# single100.net
KiCad netlist of a schematic drawn in EAGLE
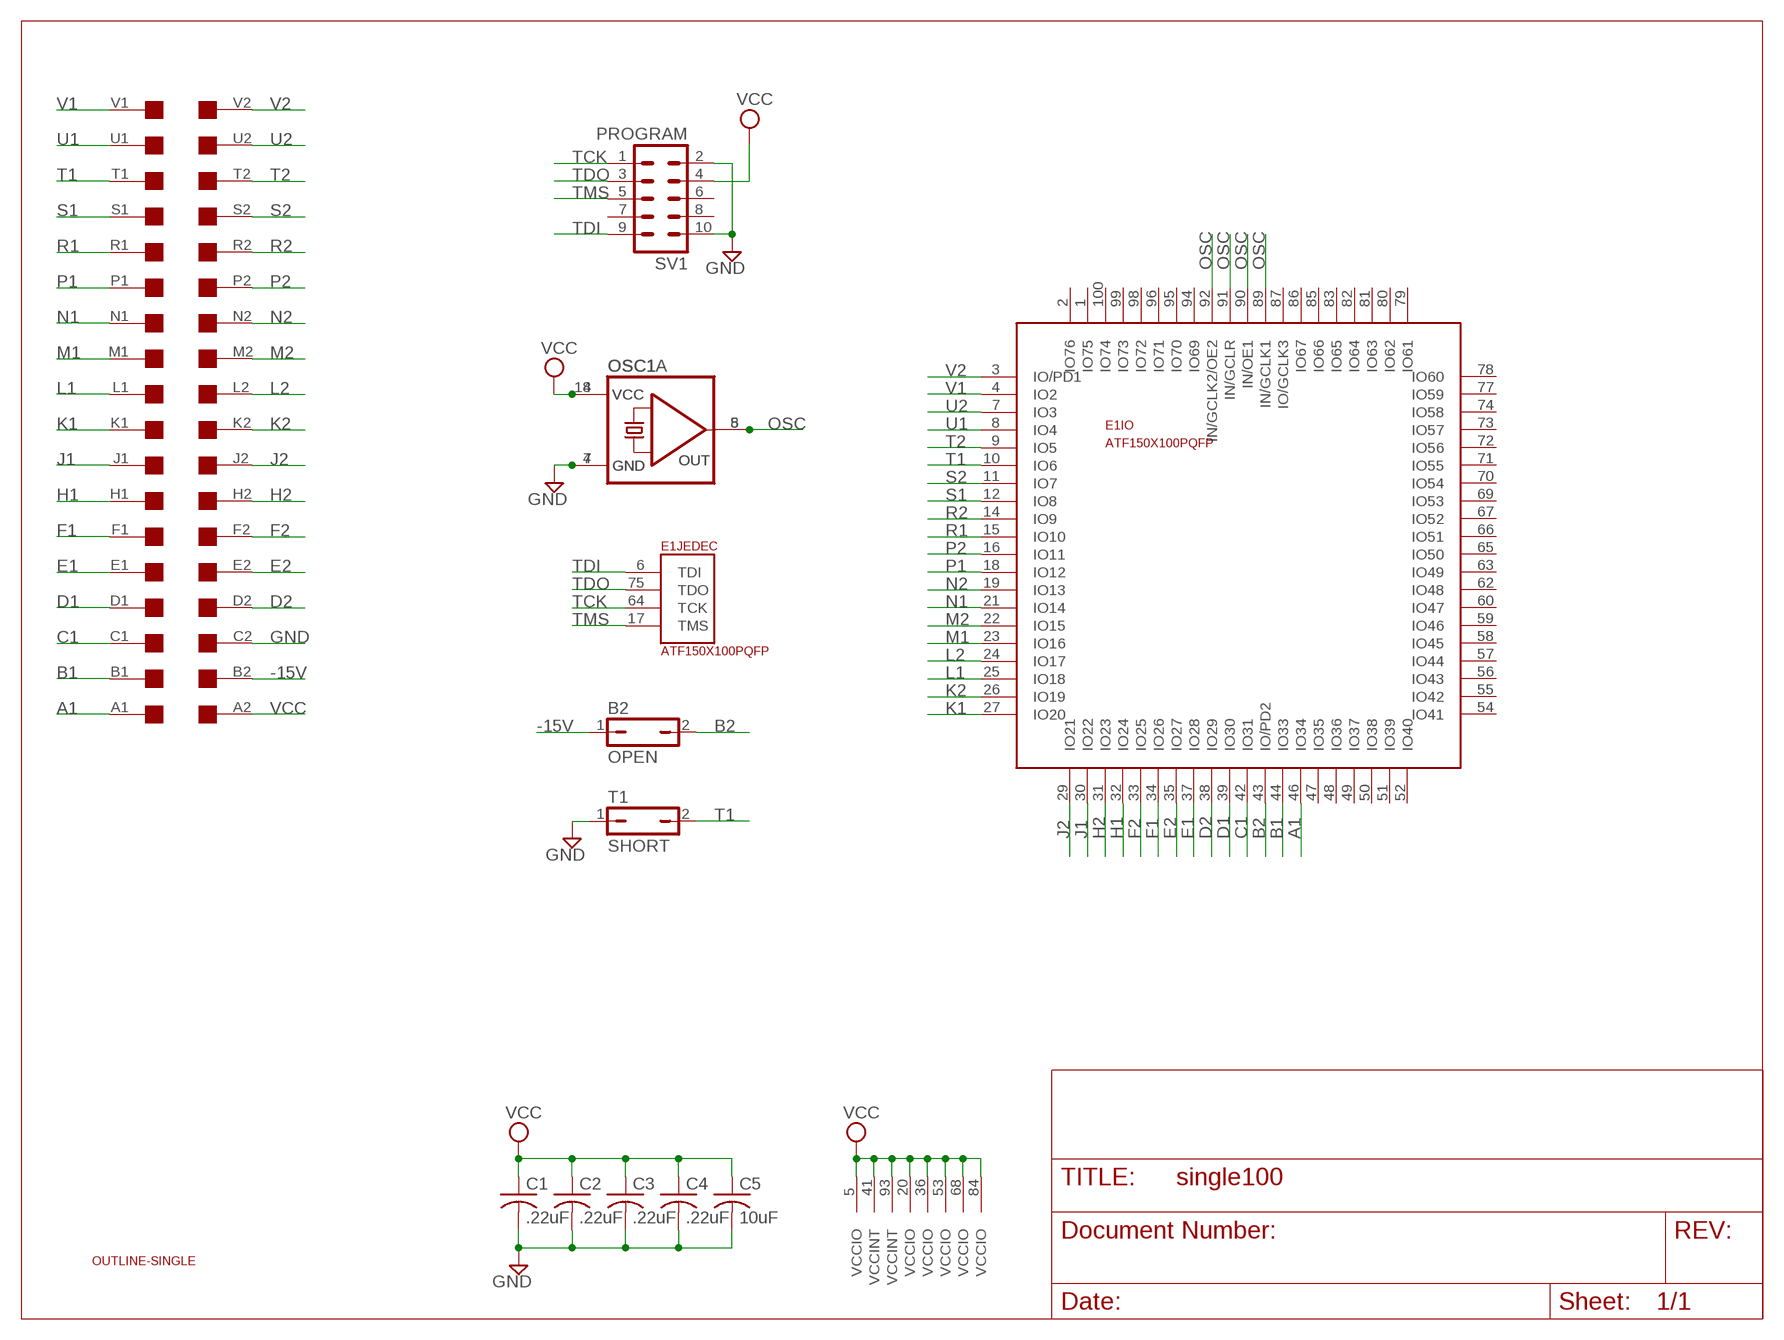
[diagram p0: schematic, sheet 1]

(export (version "E")
  (design (tool "Eeschema 10.0.6"))
  (components
    (comp (ref "B2")
      (value "OPEN")
      (footprint "eagle-import:JP1")
      (libsource (lib "eagle-import") (part "JP1Q"))
    )
    (comp (ref "C1")
      (value ".22uF")
      (footprint "eagle-import:C0805")
      (libsource (lib "eagle-import") (part "C-USC0805"))
    )
    (comp (ref "C2")
      (value ".22uF")
      (footprint "eagle-import:C0805")
      (libsource (lib "eagle-import") (part "C-USC0805"))
    )
    (comp (ref "C3")
      (value ".22uF")
      (footprint "eagle-import:C0805")
      (libsource (lib "eagle-import") (part "C-USC0805"))
    )
    (comp (ref "C4")
      (value ".22uF")
      (footprint "eagle-import:C0805")
      (libsource (lib "eagle-import") (part "C-USC0805"))
    )
    (comp (ref "C5")
      (value "10uF")
      (footprint "eagle-import:C0805")
      (libsource (lib "eagle-import") (part "C-USC0805"))
    )
    (comp (ref "E1")
      (value "ATF150X100PQFP")
      (footprint "eagle-import:PQFP-100")
      (libsource (lib "eagle-import") (part "ATF150X100PQFP"))
    )
    (comp (ref "OSC1")
      (value "QG5460")
      (footprint "eagle-import:DIL08S")
      (libsource (lib "eagle-import") (part "QG5460"))
    )
    (comp (ref "OSC1A")
      (value "QG5860")
      (footprint "eagle-import:DIL14S")
      (libsource (lib "eagle-import") (part "QG5860"))
    )
    (comp (ref "SV1")
      (value "PROGRAM")
      (footprint "eagle-import:ML10")
      (libsource (lib "eagle-import") (part "ML10"))
    )
    (comp (ref "T1")
      (value "SHORT")
      (footprint "eagle-import:JP1")
      (libsource (lib "eagle-import") (part "JP1Q"))
    )
    (comp (ref "U$1")
      (value "OUTLINE-SINGLE")
      (footprint "eagle-import:SINGLE")
      (libsource (lib "eagle-import") (part "OUTLINE-SINGLE"))
    )
    (comp (ref "U$2")
      (value "SINGLE")
      (footprint "eagle-import:EDGE-CON2")
      (libsource (lib "eagle-import") (part "SINGLE"))
    )
  )
  (nets
    (net (code "1") (name "/-15V") (class "Default")
      (node (ref "B2") (pin "1") (pinfunction "1_1") (pintype "passive"))
      (node (ref "U$2") (pin "B2") (pinfunction "1_B2") (pintype "bidirectional"))
    )
    (net (code "2") (name "/A1") (class "Default")
      (node (ref "E1") (pin "46") (pinfunction "IO34_46") (pintype "bidirectional"))
      (node (ref "U$2") (pin "A1") (pinfunction "1_A1") (pintype "bidirectional"))
    )
    (net (code "3") (name "/B1") (class "Default")
      (node (ref "E1") (pin "44") (pinfunction "IO33_44") (pintype "bidirectional"))
      (node (ref "U$2") (pin "B1") (pinfunction "1_B1") (pintype "bidirectional"))
    )
    (net (code "4") (name "/B2") (class "Default")
      (node (ref "B2") (pin "2") (pinfunction "2_2") (pintype "passive"))
      (node (ref "E1") (pin "43") (pinfunction "IO/PD2_43") (pintype "bidirectional"))
    )
    (net (code "5") (name "/C1") (class "Default")
      (node (ref "E1") (pin "42") (pinfunction "IO31_42") (pintype "bidirectional"))
      (node (ref "U$2") (pin "C1") (pinfunction "1_C1") (pintype "bidirectional"))
    )
    (net (code "6") (name "/D1") (class "Default")
      (node (ref "E1") (pin "39") (pinfunction "IO30_39") (pintype "bidirectional"))
      (node (ref "U$2") (pin "D1") (pinfunction "1_D1") (pintype "bidirectional"))
    )
    (net (code "7") (name "/D2") (class "Default")
      (node (ref "E1") (pin "38") (pinfunction "IO29_38") (pintype "bidirectional"))
      (node (ref "U$2") (pin "D2") (pinfunction "1_D2") (pintype "bidirectional"))
    )
    (net (code "8") (name "/E1") (class "Default")
      (node (ref "E1") (pin "37") (pinfunction "IO28_37") (pintype "bidirectional"))
      (node (ref "U$2") (pin "E1") (pinfunction "1_E1") (pintype "bidirectional"))
    )
    (net (code "9") (name "/E2") (class "Default")
      (node (ref "E1") (pin "35") (pinfunction "IO27_35") (pintype "bidirectional"))
      (node (ref "U$2") (pin "E2") (pinfunction "1_E2") (pintype "bidirectional"))
    )
    (net (code "10") (name "/F1") (class "Default")
      (node (ref "E1") (pin "34") (pinfunction "IO26_34") (pintype "bidirectional"))
      (node (ref "U$2") (pin "F1") (pinfunction "1_F1") (pintype "bidirectional"))
    )
    (net (code "11") (name "/F2") (class "Default")
      (node (ref "E1") (pin "33") (pinfunction "IO25_33") (pintype "bidirectional"))
      (node (ref "U$2") (pin "F2") (pinfunction "1_F2") (pintype "bidirectional"))
    )
    (net (code "12") (name "/H1") (class "Default")
      (node (ref "E1") (pin "32") (pinfunction "IO24_32") (pintype "bidirectional"))
      (node (ref "U$2") (pin "H1") (pinfunction "1_H1") (pintype "bidirectional"))
    )
    (net (code "13") (name "/H2") (class "Default")
      (node (ref "E1") (pin "31") (pinfunction "IO23_31") (pintype "bidirectional"))
      (node (ref "U$2") (pin "H2") (pinfunction "1_H2") (pintype "bidirectional"))
    )
    (net (code "14") (name "/J1") (class "Default")
      (node (ref "E1") (pin "30") (pinfunction "IO22_30") (pintype "bidirectional"))
      (node (ref "U$2") (pin "J1") (pinfunction "1_J1") (pintype "bidirectional"))
    )
    (net (code "15") (name "/J2") (class "Default")
      (node (ref "E1") (pin "29") (pinfunction "IO21_29") (pintype "bidirectional"))
      (node (ref "U$2") (pin "J2") (pinfunction "1_J2") (pintype "bidirectional"))
    )
    (net (code "16") (name "/K1") (class "Default")
      (node (ref "E1") (pin "27") (pinfunction "IO20_27") (pintype "bidirectional"))
      (node (ref "U$2") (pin "K1") (pinfunction "1_K1") (pintype "bidirectional"))
    )
    (net (code "17") (name "/K2") (class "Default")
      (node (ref "E1") (pin "26") (pinfunction "IO19_26") (pintype "bidirectional"))
      (node (ref "U$2") (pin "K2") (pinfunction "1_K2") (pintype "bidirectional"))
    )
    (net (code "18") (name "/L1") (class "Default")
      (node (ref "E1") (pin "25") (pinfunction "IO18_25") (pintype "bidirectional"))
      (node (ref "U$2") (pin "L1") (pinfunction "1_L1") (pintype "bidirectional"))
    )
    (net (code "19") (name "/L2") (class "Default")
      (node (ref "E1") (pin "24") (pinfunction "IO17_24") (pintype "bidirectional"))
      (node (ref "U$2") (pin "L2") (pinfunction "1_L2") (pintype "bidirectional"))
    )
    (net (code "20") (name "/M1") (class "Default")
      (node (ref "E1") (pin "23") (pinfunction "IO16_23") (pintype "bidirectional"))
      (node (ref "U$2") (pin "M1") (pinfunction "1_M1") (pintype "bidirectional"))
    )
    (net (code "21") (name "/M2") (class "Default")
      (node (ref "E1") (pin "22") (pinfunction "IO15_22") (pintype "bidirectional"))
      (node (ref "U$2") (pin "M2") (pinfunction "1_M2") (pintype "bidirectional"))
    )
    (net (code "22") (name "/N1") (class "Default")
      (node (ref "E1") (pin "21") (pinfunction "IO14_21") (pintype "bidirectional"))
      (node (ref "U$2") (pin "N1") (pinfunction "1_N1") (pintype "bidirectional"))
    )
    (net (code "23") (name "/N2") (class "Default")
      (node (ref "E1") (pin "19") (pinfunction "IO13_19") (pintype "bidirectional"))
      (node (ref "U$2") (pin "N2") (pinfunction "1_N2") (pintype "bidirectional"))
    )
    (net (code "24") (name "/OSC") (class "Default")
      (node (ref "E1") (pin "89") (pinfunction "IN/GCLK1_89") (pintype "input"))
      (node (ref "E1") (pin "90") (pinfunction "IN/OE1_90") (pintype "input"))
      (node (ref "E1") (pin "91") (pinfunction "IN/GCLR_91") (pintype "input"))
      (node (ref "E1") (pin "92") (pinfunction "IN/GCLK2/OE2_92") (pintype "input"))
      (node (ref "OSC1") (pin "5") (pinfunction "OUT_5") (pintype "output"))
      (node (ref "OSC1A") (pin "8") (pinfunction "OUT_8") (pintype "output"))
    )
    (net (code "25") (name "/P1") (class "Default")
      (node (ref "E1") (pin "18") (pinfunction "IO12_18") (pintype "bidirectional"))
      (node (ref "U$2") (pin "P1") (pinfunction "1_P1") (pintype "bidirectional"))
    )
    (net (code "26") (name "/P2") (class "Default")
      (node (ref "E1") (pin "16") (pinfunction "IO11_16") (pintype "bidirectional"))
      (node (ref "U$2") (pin "P2") (pinfunction "1_P2") (pintype "bidirectional"))
    )
    (net (code "27") (name "/R1") (class "Default")
      (node (ref "E1") (pin "15") (pinfunction "IO10_15") (pintype "bidirectional"))
      (node (ref "U$2") (pin "R1") (pinfunction "1_R1") (pintype "bidirectional"))
    )
    (net (code "28") (name "/R2") (class "Default")
      (node (ref "E1") (pin "14") (pinfunction "IO9_14") (pintype "bidirectional"))
      (node (ref "U$2") (pin "R2") (pinfunction "1_R2") (pintype "bidirectional"))
    )
    (net (code "29") (name "/S1") (class "Default")
      (node (ref "E1") (pin "12") (pinfunction "IO8_12") (pintype "bidirectional"))
      (node (ref "U$2") (pin "S1") (pinfunction "1_S1") (pintype "bidirectional"))
    )
    (net (code "30") (name "/S2") (class "Default")
      (node (ref "E1") (pin "11") (pinfunction "IO7_11") (pintype "bidirectional"))
      (node (ref "U$2") (pin "S2") (pinfunction "1_S2") (pintype "bidirectional"))
    )
    (net (code "31") (name "/T1") (class "Default")
      (node (ref "E1") (pin "10") (pinfunction "IO6_10") (pintype "bidirectional"))
      (node (ref "T1") (pin "2") (pinfunction "2_2") (pintype "passive"))
      (node (ref "U$2") (pin "T1") (pinfunction "1_T1") (pintype "bidirectional"))
    )
    (net (code "32") (name "/T2") (class "Default")
      (node (ref "E1") (pin "9") (pinfunction "IO5_9") (pintype "bidirectional"))
      (node (ref "U$2") (pin "T2") (pinfunction "1_T2") (pintype "bidirectional"))
    )
    (net (code "33") (name "/TCK") (class "Default")
      (node (ref "E1") (pin "64") (pinfunction "TCK_64") (pintype "bidirectional"))
      (node (ref "SV1") (pin "1") (pinfunction "1_1") (pintype "passive"))
    )
    (net (code "34") (name "/TDI") (class "Default")
      (node (ref "E1") (pin "6") (pinfunction "TDI_6") (pintype "bidirectional"))
      (node (ref "SV1") (pin "9") (pinfunction "9_9") (pintype "passive"))
    )
    (net (code "35") (name "/TDO") (class "Default")
      (node (ref "E1") (pin "75") (pinfunction "TDO_75") (pintype "bidirectional"))
      (node (ref "SV1") (pin "3") (pinfunction "3_3") (pintype "passive"))
    )
    (net (code "36") (name "/TMS") (class "Default")
      (node (ref "E1") (pin "17") (pinfunction "TMS_17") (pintype "bidirectional"))
      (node (ref "SV1") (pin "5") (pinfunction "5_5") (pintype "passive"))
    )
    (net (code "37") (name "/U1") (class "Default")
      (node (ref "E1") (pin "8") (pinfunction "IO4_8") (pintype "bidirectional"))
      (node (ref "U$2") (pin "U1") (pinfunction "1_U1") (pintype "bidirectional"))
    )
    (net (code "38") (name "/U2") (class "Default")
      (node (ref "E1") (pin "7") (pinfunction "IO3_7") (pintype "bidirectional"))
      (node (ref "U$2") (pin "U2") (pinfunction "1_U2") (pintype "bidirectional"))
    )
    (net (code "39") (name "/V1") (class "Default")
      (node (ref "E1") (pin "4") (pinfunction "IO2_4") (pintype "bidirectional"))
      (node (ref "U$2") (pin "V1") (pinfunction "1_V1") (pintype "bidirectional"))
    )
    (net (code "40") (name "/V2") (class "Default")
      (node (ref "E1") (pin "3") (pinfunction "IO/PD1_3") (pintype "bidirectional"))
      (node (ref "U$2") (pin "V2") (pinfunction "1_V2") (pintype "bidirectional"))
    )
    (net (code "41") (name "GND") (class "Default")
      (node (ref "C1") (pin "2") (pinfunction "2_2") (pintype "passive"))
      (node (ref "C2") (pin "2") (pinfunction "2_2") (pintype "passive"))
      (node (ref "C3") (pin "2") (pinfunction "2_2") (pintype "passive"))
      (node (ref "C4") (pin "2") (pinfunction "2_2") (pintype "passive"))
      (node (ref "C5") (pin "2") (pinfunction "2_2") (pintype "passive"))
      (node (ref "OSC1") (pin "4") (pinfunction "GND_4") (pintype "power_in"))
      (node (ref "OSC1A") (pin "7") (pinfunction "GND_7") (pintype "power_in"))
      (node (ref "SV1") (pin "10") (pinfunction "10_10") (pintype "passive"))
      (node (ref "SV1") (pin "2") (pinfunction "2_2") (pintype "passive"))
      (node (ref "T1") (pin "1") (pinfunction "1_1") (pintype "passive"))
      (node (ref "U$2") (pin "C2") (pinfunction "1_C2") (pintype "bidirectional"))
    )
    (net (code "42") (name "VCC") (class "Default")
      (node (ref "C1") (pin "1") (pinfunction "1_1") (pintype "passive"))
      (node (ref "C2") (pin "1") (pinfunction "1_1") (pintype "passive"))
      (node (ref "C3") (pin "1") (pinfunction "1_1") (pintype "passive"))
      (node (ref "C4") (pin "1") (pinfunction "1_1") (pintype "passive"))
      (node (ref "C5") (pin "1") (pinfunction "1_1") (pintype "passive"))
      (node (ref "E1") (pin "20") (pinfunction "VCCIO_20") (pintype "power_in"))
      (node (ref "E1") (pin "36") (pinfunction "VCCIO_36") (pintype "power_in"))
      (node (ref "E1") (pin "41") (pinfunction "VCCINT_41") (pintype "power_in"))
      (node (ref "E1") (pin "5") (pinfunction "VCCIO_5") (pintype "power_in"))
      (node (ref "E1") (pin "53") (pinfunction "VCCIO_53") (pintype "power_in"))
      (node (ref "E1") (pin "68") (pinfunction "VCCIO_68") (pintype "power_in"))
      (node (ref "E1") (pin "84") (pinfunction "VCCIO_84") (pintype "power_in"))
      (node (ref "E1") (pin "93") (pinfunction "VCCINT_93") (pintype "power_in"))
      (node (ref "OSC1") (pin "8") (pinfunction "VCC_8") (pintype "power_in"))
      (node (ref "OSC1A") (pin "14") (pinfunction "VCC_14") (pintype "power_in"))
      (node (ref "SV1") (pin "4") (pinfunction "4_4") (pintype "passive"))
      (node (ref "U$2") (pin "A2") (pinfunction "1_A2") (pintype "bidirectional"))
    )
    (net (code "43") (name "unconnected-(E1Q-IO35-Pad47)") (class "Default")
      (node (ref "E1") (pin "47") (pinfunction "IO35_47") (pintype "bidirectional"))
    )
    (net (code "44") (name "unconnected-(E1Q-IO36-Pad48)") (class "Default")
      (node (ref "E1") (pin "48") (pinfunction "IO36_48") (pintype "bidirectional"))
    )
    (net (code "45") (name "unconnected-(E1Q-IO37-Pad49)") (class "Default")
      (node (ref "E1") (pin "49") (pinfunction "IO37_49") (pintype "bidirectional"))
    )
    (net (code "46") (name "unconnected-(E1Q-IO38-Pad50)") (class "Default")
      (node (ref "E1") (pin "50") (pinfunction "IO38_50") (pintype "bidirectional"))
    )
    (net (code "47") (name "unconnected-(E1Q-IO39-Pad51)") (class "Default")
      (node (ref "E1") (pin "51") (pinfunction "IO39_51") (pintype "bidirectional"))
    )
    (net (code "48") (name "unconnected-(E1Q-IO40-Pad52)") (class "Default")
      (node (ref "E1") (pin "52") (pinfunction "IO40_52") (pintype "bidirectional"))
    )
    (net (code "49") (name "unconnected-(E1Q-IO41-Pad54)") (class "Default")
      (node (ref "E1") (pin "54") (pinfunction "IO41_54") (pintype "bidirectional"))
    )
    (net (code "50") (name "unconnected-(E1Q-IO42-Pad55)") (class "Default")
      (node (ref "E1") (pin "55") (pinfunction "IO42_55") (pintype "bidirectional"))
    )
    (net (code "51") (name "unconnected-(E1Q-IO43-Pad56)") (class "Default")
      (node (ref "E1") (pin "56") (pinfunction "IO43_56") (pintype "bidirectional"))
    )
    (net (code "52") (name "unconnected-(E1Q-IO44-Pad57)") (class "Default")
      (node (ref "E1") (pin "57") (pinfunction "IO44_57") (pintype "bidirectional"))
    )
    (net (code "53") (name "unconnected-(E1Q-IO45-Pad58)") (class "Default")
      (node (ref "E1") (pin "58") (pinfunction "IO45_58") (pintype "bidirectional"))
    )
    (net (code "54") (name "unconnected-(E1Q-IO46-Pad59)") (class "Default")
      (node (ref "E1") (pin "59") (pinfunction "IO46_59") (pintype "bidirectional"))
    )
    (net (code "55") (name "unconnected-(E1Q-IO47-Pad60)") (class "Default")
      (node (ref "E1") (pin "60") (pinfunction "IO47_60") (pintype "bidirectional"))
    )
    (net (code "56") (name "unconnected-(E1Q-IO48-Pad62)") (class "Default")
      (node (ref "E1") (pin "62") (pinfunction "IO48_62") (pintype "bidirectional"))
    )
    (net (code "57") (name "unconnected-(E1Q-IO49-Pad63)") (class "Default")
      (node (ref "E1") (pin "63") (pinfunction "IO49_63") (pintype "bidirectional"))
    )
    (net (code "58") (name "unconnected-(E1Q-IO50-Pad65)") (class "Default")
      (node (ref "E1") (pin "65") (pinfunction "IO50_65") (pintype "bidirectional"))
    )
    (net (code "59") (name "unconnected-(E1Q-IO51-Pad66)") (class "Default")
      (node (ref "E1") (pin "66") (pinfunction "IO51_66") (pintype "bidirectional"))
    )
    (net (code "60") (name "unconnected-(E1Q-IO52-Pad67)") (class "Default")
      (node (ref "E1") (pin "67") (pinfunction "IO52_67") (pintype "bidirectional"))
    )
    (net (code "61") (name "unconnected-(E1Q-IO53-Pad69)") (class "Default")
      (node (ref "E1") (pin "69") (pinfunction "IO53_69") (pintype "bidirectional"))
    )
    (net (code "62") (name "unconnected-(E1Q-IO54-Pad70)") (class "Default")
      (node (ref "E1") (pin "70") (pinfunction "IO54_70") (pintype "bidirectional"))
    )
    (net (code "63") (name "unconnected-(E1Q-IO55-Pad71)") (class "Default")
      (node (ref "E1") (pin "71") (pinfunction "IO55_71") (pintype "bidirectional"))
    )
    (net (code "64") (name "unconnected-(E1Q-IO56-Pad72)") (class "Default")
      (node (ref "E1") (pin "72") (pinfunction "IO56_72") (pintype "bidirectional"))
    )
    (net (code "65") (name "unconnected-(E1Q-IO57-Pad73)") (class "Default")
      (node (ref "E1") (pin "73") (pinfunction "IO57_73") (pintype "bidirectional"))
    )
    (net (code "66") (name "unconnected-(E1Q-IO58-Pad74)") (class "Default")
      (node (ref "E1") (pin "74") (pinfunction "IO58_74") (pintype "bidirectional"))
    )
    (net (code "67") (name "unconnected-(E1Q-IO59-Pad77)") (class "Default")
      (node (ref "E1") (pin "77") (pinfunction "IO59_77") (pintype "bidirectional"))
    )
    (net (code "68") (name "unconnected-(E1Q-IO60-Pad78)") (class "Default")
      (node (ref "E1") (pin "78") (pinfunction "IO60_78") (pintype "bidirectional"))
    )
    (net (code "69") (name "unconnected-(E1Q-IO61-Pad79)") (class "Default")
      (node (ref "E1") (pin "79") (pinfunction "IO61_79") (pintype "bidirectional"))
    )
    (net (code "70") (name "unconnected-(E1Q-IO62-Pad80)") (class "Default")
      (node (ref "E1") (pin "80") (pinfunction "IO62_80") (pintype "bidirectional"))
    )
    (net (code "71") (name "unconnected-(E1Q-IO63-Pad81)") (class "Default")
      (node (ref "E1") (pin "81") (pinfunction "IO63_81") (pintype "bidirectional"))
    )
    (net (code "72") (name "unconnected-(E1Q-IO64-Pad82)") (class "Default")
      (node (ref "E1") (pin "82") (pinfunction "IO64_82") (pintype "bidirectional"))
    )
    (net (code "73") (name "unconnected-(E1Q-IO65-Pad83)") (class "Default")
      (node (ref "E1") (pin "83") (pinfunction "IO65_83") (pintype "bidirectional"))
    )
    (net (code "74") (name "unconnected-(E1Q-IO66-Pad85)") (class "Default")
      (node (ref "E1") (pin "85") (pinfunction "IO66_85") (pintype "bidirectional"))
    )
    (net (code "75") (name "unconnected-(E1Q-IO67-Pad86)") (class "Default")
      (node (ref "E1") (pin "86") (pinfunction "IO67_86") (pintype "bidirectional"))
    )
    (net (code "76") (name "unconnected-(E1Q-IO69-Pad94)") (class "Default")
      (node (ref "E1") (pin "94") (pinfunction "IO69_94") (pintype "bidirectional"))
    )
    (net (code "77") (name "unconnected-(E1Q-IO70-Pad95)") (class "Default")
      (node (ref "E1") (pin "95") (pinfunction "IO70_95") (pintype "bidirectional"))
    )
    (net (code "78") (name "unconnected-(E1Q-IO71-Pad96)") (class "Default")
      (node (ref "E1") (pin "96") (pinfunction "IO71_96") (pintype "bidirectional"))
    )
    (net (code "79") (name "unconnected-(E1Q-IO72-Pad98)") (class "Default")
      (node (ref "E1") (pin "98") (pinfunction "IO72_98") (pintype "bidirectional"))
    )
    (net (code "80") (name "unconnected-(E1Q-IO73-Pad99)") (class "Default")
      (node (ref "E1") (pin "99") (pinfunction "IO73_99") (pintype "bidirectional"))
    )
    (net (code "81") (name "unconnected-(E1Q-IO74-Pad100)") (class "Default")
      (node (ref "E1") (pin "100") (pinfunction "IO74_100") (pintype "bidirectional"))
    )
    (net (code "82") (name "unconnected-(E1Q-IO75-Pad1)") (class "Default")
      (node (ref "E1") (pin "1") (pinfunction "IO75_1") (pintype "bidirectional"))
    )
    (net (code "83") (name "unconnected-(E1Q-IO76-Pad2)") (class "Default")
      (node (ref "E1") (pin "2") (pinfunction "IO76_2") (pintype "bidirectional"))
    )
    (net (code "84") (name "unconnected-(E1Q-IO{slash}GCLK3-Pad87)") (class "Default")
      (node (ref "E1") (pin "87") (pinfunction "IO/GCLK3_87") (pintype "bidirectional"))
    )
    (net (code "85") (name "unconnected-(SV1-Pad6)") (class "Default")
      (node (ref "SV1") (pin "6") (pinfunction "6_6") (pintype "passive"))
    )
    (net (code "86") (name "unconnected-(SV1-Pad7)") (class "Default")
      (node (ref "SV1") (pin "7") (pinfunction "7_7") (pintype "passive"))
    )
    (net (code "87") (name "unconnected-(SV1-Pad8)") (class "Default")
      (node (ref "SV1") (pin "8") (pinfunction "8_8") (pintype "passive"))
    )
  )
)
